# Differential_Pair_Setup.net
KiCad netlist of a schematic drawn in Altium Designer
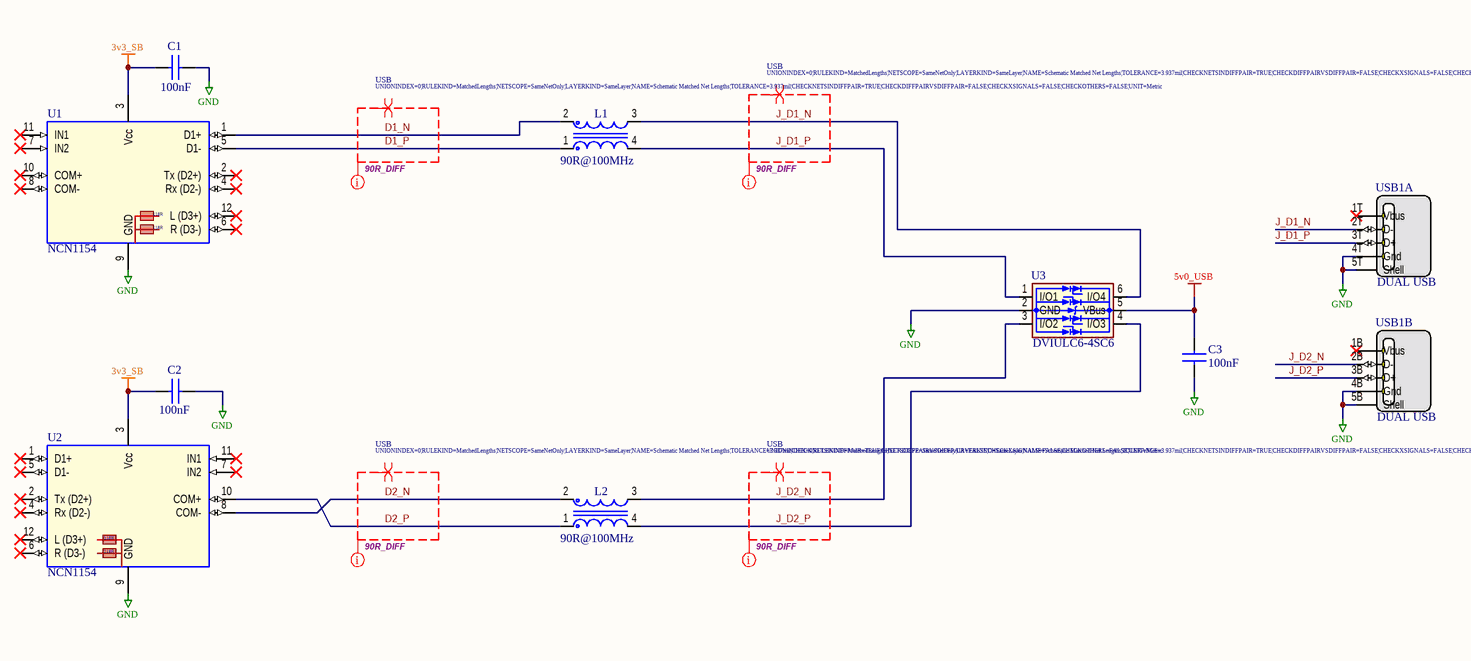
[diagram p0: Differential Pair Setup.SchDoc]

(export (version "E")
  (design (tool "Eeschema 10.0.6"))
  (components
    (comp (ref "C1")
      (value "100nF")
      (footprint "CC0402")
      (description "Cap, 100nF, X7R, 16V, ±10%, CC0402")
      (libsource (lib "xSignal_Differential_Pairs") (part "CAP_100nF"))
    )
    (comp (ref "C2")
      (value "100nF")
      (footprint "CC0402")
      (description "Cap, 100nF, X7R, 16V, ±10%, CC0402")
      (libsource (lib "xSignal_Differential_Pairs") (part "CAP_100nF"))
    )
    (comp (ref "C3")
      (value "100nF")
      (footprint "CC0402")
      (description "Cap, 100nF, X7R, 16V, ±10%, CC0402")
      (libsource (lib "xSignal_Differential_Pairs") (part "CAP_100nF"))
    )
    (comp (ref "L1")
      (value "90R@100MHz")
      (footprint "ACM2012")
      (description "CMNCK, 90R@100MHz, 50V, 400mA, ACM2012")
      (libsource (lib "xSignal_Differential_Pairs") (part "FILTER"))
    )
    (comp (ref "L2")
      (value "90R@100MHz")
      (footprint "ACM2012")
      (description "CMNCK, 90R@100MHz, 50V, 400mA, ACM2012")
      (libsource (lib "xSignal_Differential_Pairs") (part "FILTER"))
    )
    (comp (ref "U1")
      (value "NCN1154")
      (footprint "UQFN12")
      (description "3:1 High-Speed USB /UART/Auido Mux")
      (libsource (lib "xSignal_Differential_Pairs") (part "USB_UART"))
    )
    (comp (ref "U2")
      (value "NCN1154")
      (footprint "UQFN12")
      (description "3:1 High-Speed USB /UART/Auido Mux")
      (libsource (lib "") (part "USB_UART_1"))
    )
    (comp (ref "U3")
      (value "DVIULC6-4SC6")
      (footprint "SOT23-6L")
      (description "4-chl Ultra-Low Capacitance ESD protector with TVS diode")
      (libsource (lib "xSignal_Differential_Pairs") (part "ESD_Protector"))
    )
    (comp (ref "USB1")
      (value "DUAL USB")
      (footprint "USB-A_RA_DUAL")
      (libsource (lib "xSignal_Differential_Pairs") (part "USB"))
    )
  )
  (nets
    (net (code "1") (name "/D1_N") (class "Default")
      (node (ref "L1") (pin "2") (pinfunction "2_2") (pintype "passive"))
      (node (ref "U1") (pin "1") (pinfunction "D1+_1") (pintype "bidirectional"))
    )
    (net (code "2") (name "/D1_P") (class "Default")
      (node (ref "L1") (pin "1") (pinfunction "1_1") (pintype "passive"))
      (node (ref "U1") (pin "5") (pinfunction "D1-_5") (pintype "bidirectional"))
    )
    (net (code "3") (name "/D2_N") (class "Default")
      (node (ref "L2") (pin "2") (pinfunction "2_2") (pintype "passive"))
      (node (ref "U2") (pin "8") (pinfunction "COM-_8") (pintype "bidirectional"))
    )
    (net (code "4") (name "/D2_P") (class "Default")
      (node (ref "L2") (pin "1") (pinfunction "1_1") (pintype "passive"))
      (node (ref "U2") (pin "10") (pinfunction "COM+_10") (pintype "bidirectional"))
    )
    (net (code "5") (name "/J_D1_N") (class "Default")
      (node (ref "L1") (pin "3") (pinfunction "3_3") (pintype "passive"))
      (node (ref "U3") (pin "6") (pinfunction "I/O4_6") (pintype "passive"))
      (node (ref "USB1") (pin "2T") (pinfunction "D-_2T") (pintype "bidirectional"))
    )
    (net (code "6") (name "/J_D1_P") (class "Default")
      (node (ref "L1") (pin "4") (pinfunction "4_4") (pintype "passive"))
      (node (ref "U3") (pin "1") (pinfunction "I/O1_1") (pintype "passive"))
      (node (ref "USB1") (pin "3T") (pinfunction "D+_3T") (pintype "bidirectional"))
    )
    (net (code "7") (name "/J_D2_N") (class "Default")
      (node (ref "L2") (pin "3") (pinfunction "3_3") (pintype "passive"))
      (node (ref "U3") (pin "3") (pinfunction "I/O2_3") (pintype "passive"))
      (node (ref "USB1") (pin "2B") (pinfunction "D-_2B") (pintype "bidirectional"))
    )
    (net (code "8") (name "/J_D2_P") (class "Default")
      (node (ref "L2") (pin "4") (pinfunction "4_4") (pintype "passive"))
      (node (ref "U3") (pin "4") (pinfunction "I/O3_4") (pintype "passive"))
      (node (ref "USB1") (pin "3B") (pinfunction "D+_3B") (pintype "bidirectional"))
    )
    (net (code "9") (name "3v3_SB") (class "Default")
      (node (ref "C1") (pin "2") (pinfunction "2_2") (pintype "passive"))
      (node (ref "C2") (pin "2") (pinfunction "2_2") (pintype "passive"))
      (node (ref "U1") (pin "3") (pinfunction "Vcc_3") (pintype "power_in"))
      (node (ref "U2") (pin "3") (pinfunction "Vcc_3") (pintype "power_in"))
    )
    (net (code "10") (name "5v0_USB") (class "Default")
      (node (ref "C3") (pin "1") (pinfunction "1_1") (pintype "passive"))
      (node (ref "U3") (pin "5") (pinfunction "VBus_5") (pintype "passive"))
    )
    (net (code "11") (name "GND") (class "Default")
      (node (ref "C1") (pin "1") (pinfunction "1_1") (pintype "passive"))
      (node (ref "C2") (pin "1") (pinfunction "1_1") (pintype "passive"))
      (node (ref "C3") (pin "2") (pinfunction "2_2") (pintype "passive"))
      (node (ref "U1") (pin "9") (pinfunction "GND_9") (pintype "power_in"))
      (node (ref "U2") (pin "9") (pinfunction "GND_9") (pintype "power_in"))
      (node (ref "U3") (pin "2") (pinfunction "GND_2") (pintype "passive"))
      (node (ref "USB1") (pin "4B") (pinfunction "Gnd_4B") (pintype "power_in"))
      (node (ref "USB1") (pin "4T") (pinfunction "Gnd_4T") (pintype "power_in"))
      (node (ref "USB1") (pin "5B") (pinfunction "Shell_5B") (pintype "power_in"))
      (node (ref "USB1") (pin "5T") (pinfunction "Shell_5T") (pintype "power_in"))
    )
    (net (code "12") (name "unconnected-(U1-COM+-Pad10)") (class "Default")
      (node (ref "U1") (pin "10") (pinfunction "COM+_10") (pintype "bidirectional+no_connect"))
    )
    (net (code "13") (name "unconnected-(U1-COM--Pad8)") (class "Default")
      (node (ref "U1") (pin "8") (pinfunction "COM-_8") (pintype "bidirectional+no_connect"))
    )
    (net (code "14") (name "unconnected-(U1-IN1-Pad11)") (class "Default")
      (node (ref "U1") (pin "11") (pinfunction "IN1_11") (pintype "input+no_connect"))
    )
    (net (code "15") (name "unconnected-(U1-IN2-Pad7)") (class "Default")
      (node (ref "U1") (pin "7") (pinfunction "IN2_7") (pintype "input+no_connect"))
    )
    (net (code "16") (name "unconnected-(U1-L_(D3+)-Pad12)") (class "Default")
      (node (ref "U1") (pin "12") (pinfunction "L_(D3+)_12") (pintype "bidirectional+no_connect"))
    )
    (net (code "17") (name "unconnected-(U1-R_(D3-)-Pad6)") (class "Default")
      (node (ref "U1") (pin "6") (pinfunction "R_(D3-)_6") (pintype "bidirectional+no_connect"))
    )
    (net (code "18") (name "unconnected-(U1-Rx_(D2-)-Pad4)") (class "Default")
      (node (ref "U1") (pin "4") (pinfunction "Rx_(D2-)_4") (pintype "bidirectional+no_connect"))
    )
    (net (code "19") (name "unconnected-(U1-Tx_(D2+)-Pad2)") (class "Default")
      (node (ref "U1") (pin "2") (pinfunction "Tx_(D2+)_2") (pintype "bidirectional+no_connect"))
    )
    (net (code "20") (name "unconnected-(U2-D1+-Pad1)") (class "Default")
      (node (ref "U2") (pin "1") (pinfunction "D1+_1") (pintype "bidirectional+no_connect"))
    )
    (net (code "21") (name "unconnected-(U2-D1--Pad5)") (class "Default")
      (node (ref "U2") (pin "5") (pinfunction "D1-_5") (pintype "bidirectional+no_connect"))
    )
    (net (code "22") (name "unconnected-(U2-IN1-Pad11)") (class "Default")
      (node (ref "U2") (pin "11") (pinfunction "IN1_11") (pintype "input+no_connect"))
    )
    (net (code "23") (name "unconnected-(U2-IN2-Pad7)") (class "Default")
      (node (ref "U2") (pin "7") (pinfunction "IN2_7") (pintype "input+no_connect"))
    )
    (net (code "24") (name "unconnected-(U2-L_(D3+)-Pad12)") (class "Default")
      (node (ref "U2") (pin "12") (pinfunction "L_(D3+)_12") (pintype "bidirectional+no_connect"))
    )
    (net (code "25") (name "unconnected-(U2-R_(D3-)-Pad6)") (class "Default")
      (node (ref "U2") (pin "6") (pinfunction "R_(D3-)_6") (pintype "bidirectional+no_connect"))
    )
    (net (code "26") (name "unconnected-(U2-Rx_(D2-)-Pad4)") (class "Default")
      (node (ref "U2") (pin "4") (pinfunction "Rx_(D2-)_4") (pintype "bidirectional+no_connect"))
    )
    (net (code "27") (name "unconnected-(U2-Tx_(D2+)-Pad2)") (class "Default")
      (node (ref "U2") (pin "2") (pinfunction "Tx_(D2+)_2") (pintype "bidirectional+no_connect"))
    )
    (net (code "28") (name "unconnected-(USB1A-Vbus-Pad1T)") (class "Default")
      (node (ref "USB1") (pin "1T") (pinfunction "Vbus_1T") (pintype "power_in+no_connect"))
    )
    (net (code "29") (name "unconnected-(USB1B-Vbus-Pad1B)") (class "Default")
      (node (ref "USB1") (pin "1B") (pinfunction "Vbus_1B") (pintype "power_in+no_connect"))
    )
  )
)
